# main.net
KiCad netlist of a schematic drawn in Altium Designer
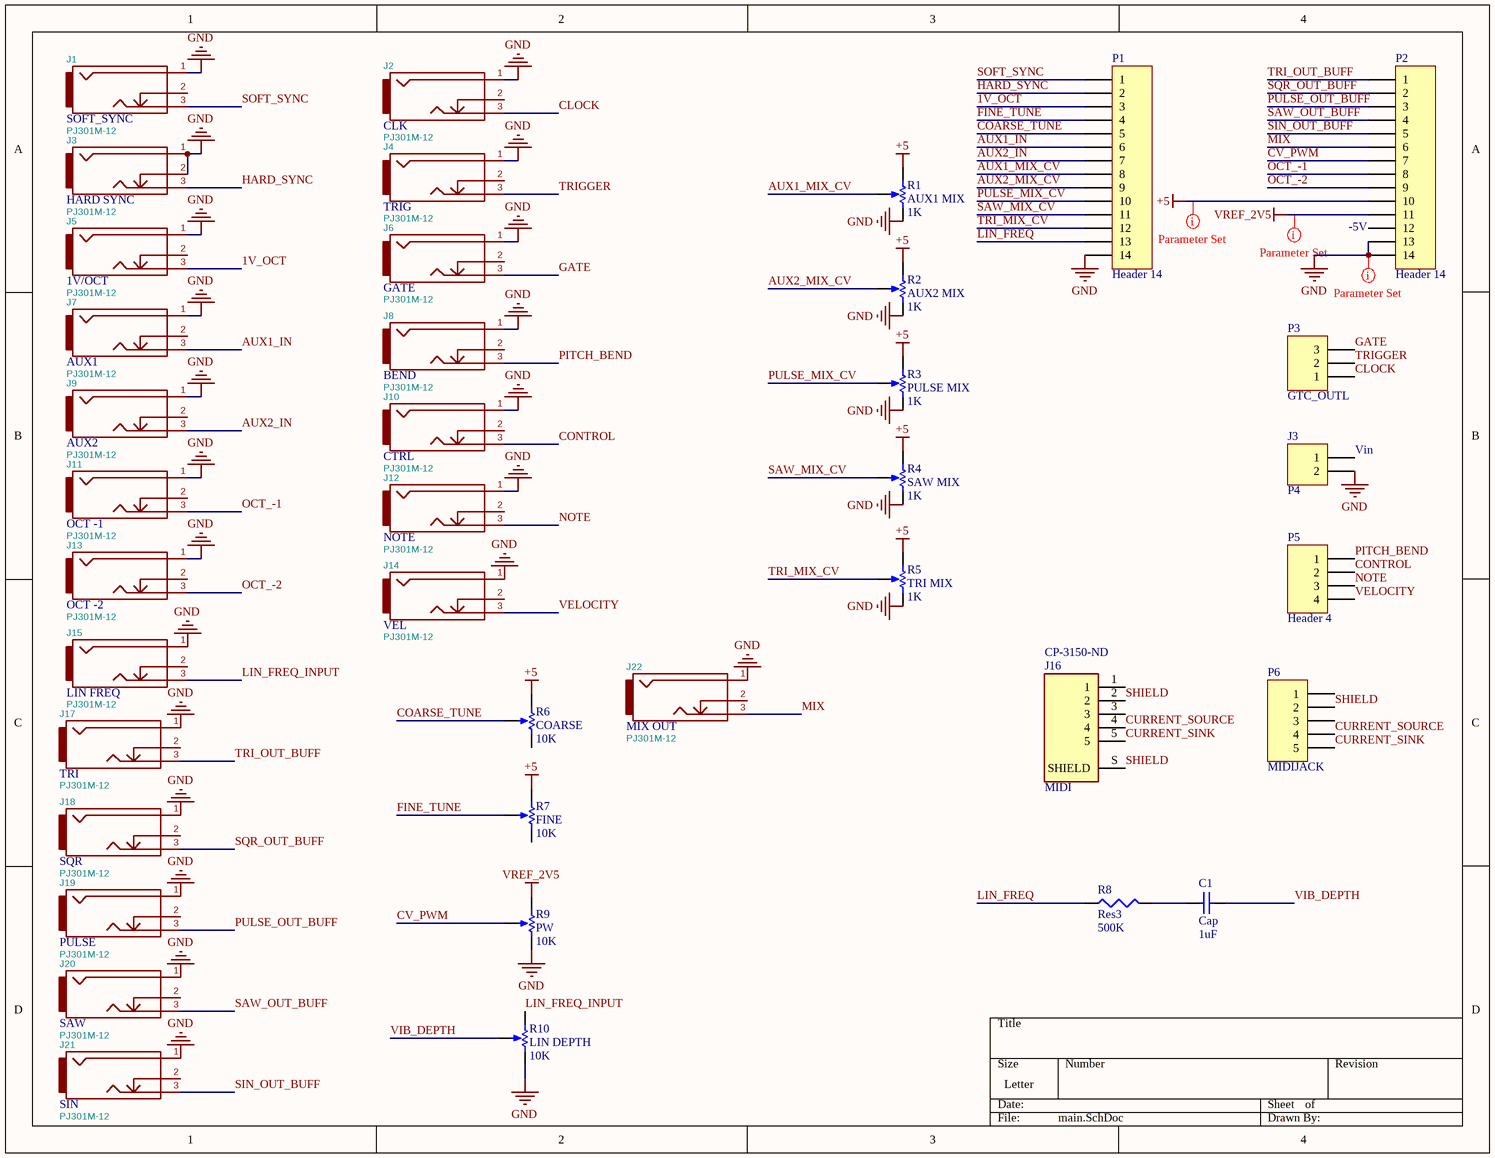
[diagram p0: main.SchDoc]

(export (version "E")
  (design (tool "Eeschema 10.0.6"))
  (components
    (comp (ref "C1")
      (value "Cap")
      (footprint "C1206")
      (description "Capacitor")
      (fields (field (name "ALTIUM_VALUE") "1uF") (field (name "PUBLISHER") "Altium Limited"))
      (libsource (lib "Miscellaneous Devices") (part "Cap"))
    )
    (comp (ref "J1")
      (value "SOFT_SYNC")
      (footprint "PJ301M-12")
      (fields (field (name "ALTIUM_VALUE") "PJ301M-12"))
      (libsource (lib "eurocad") (part "PJ301M-12"))
    )
    (comp (ref "J2")
      (value "CLK")
      (footprint "PJ301M-12")
      (fields (field (name "ALTIUM_VALUE") "PJ301M-12"))
      (libsource (lib "eurocad") (part "PJ301M-12"))
    )
    (comp (ref "J3")
      (value "HARD SYNC")
      (footprint "PJ301M-12")
      (fields (field (name "ALTIUM_VALUE") "PJ301M-12"))
      (libsource (lib "eurocad") (part "PJ301M-12"))
    )
    (comp (ref "J4")
      (value "TRIG")
      (footprint "PJ301M-12")
      (fields (field (name "ALTIUM_VALUE") "PJ301M-12"))
      (libsource (lib "eurocad") (part "PJ301M-12"))
    )
    (comp (ref "J5")
      (value "1V/OCT")
      (footprint "PJ301M-12")
      (fields (field (name "ALTIUM_VALUE") "PJ301M-12"))
      (libsource (lib "eurocad") (part "PJ301M-12"))
    )
    (comp (ref "J6")
      (value "GATE")
      (footprint "PJ301M-12")
      (fields (field (name "ALTIUM_VALUE") "PJ301M-12"))
      (libsource (lib "eurocad") (part "PJ301M-12"))
    )
    (comp (ref "J7")
      (value "AUX1")
      (footprint "PJ301M-12")
      (fields (field (name "ALTIUM_VALUE") "PJ301M-12"))
      (libsource (lib "eurocad") (part "PJ301M-12"))
    )
    (comp (ref "J8")
      (value "BEND")
      (footprint "PJ301M-12")
      (fields (field (name "ALTIUM_VALUE") "PJ301M-12"))
      (libsource (lib "eurocad") (part "PJ301M-12"))
    )
    (comp (ref "J9")
      (value "AUX2")
      (footprint "PJ301M-12")
      (fields (field (name "ALTIUM_VALUE") "PJ301M-12"))
      (libsource (lib "eurocad") (part "PJ301M-12"))
    )
    (comp (ref "J10")
      (value "CTRL")
      (footprint "PJ301M-12")
      (fields (field (name "ALTIUM_VALUE") "PJ301M-12"))
      (libsource (lib "eurocad") (part "PJ301M-12"))
    )
    (comp (ref "J11")
      (value "OCT -1")
      (footprint "PJ301M-12")
      (fields (field (name "ALTIUM_VALUE") "PJ301M-12"))
      (libsource (lib "eurocad") (part "PJ301M-12"))
    )
    (comp (ref "J12")
      (value "NOTE")
      (footprint "PJ301M-12")
      (fields (field (name "ALTIUM_VALUE") "PJ301M-12"))
      (libsource (lib "eurocad") (part "PJ301M-12"))
    )
    (comp (ref "J13")
      (value "OCT -2")
      (footprint "PJ301M-12")
      (fields (field (name "ALTIUM_VALUE") "PJ301M-12"))
      (libsource (lib "eurocad") (part "PJ301M-12"))
    )
    (comp (ref "J14")
      (value "VEL")
      (footprint "PJ301M-12")
      (fields (field (name "ALTIUM_VALUE") "PJ301M-12"))
      (libsource (lib "eurocad") (part "PJ301M-12"))
    )
    (comp (ref "J15")
      (value "LIN FREQ")
      (footprint "PJ301M-12")
      (fields (field (name "ALTIUM_VALUE") "PJ301M-12"))
      (libsource (lib "eurocad") (part "PJ301M-12"))
    )
    (comp (ref "J16")
      (value "MIDI")
      (footprint "CUI_SD-50BV")
      (description "3~8 Positions, Receptacle, Vertical, Through Hole, Shielded, Standard Circular DIN Connector")
      (fields
        (field (name "MP") "SD-50BV")
        (field (name "MF") "CUI Devices")
        (field (name "SUPPLIER PART NUMBER 1") "CP-3150-ND")
      )
      (libsource (lib "SD-50BV") (part "SD-50BV"))
    )
    (comp (ref "J17")
      (value "TRI")
      (footprint "PJ301M-12")
      (fields (field (name "ALTIUM_VALUE") "PJ301M-12"))
      (libsource (lib "eurocad") (part "PJ301M-12"))
    )
    (comp (ref "J18")
      (value "SQR")
      (footprint "PJ301M-12")
      (fields (field (name "ALTIUM_VALUE") "PJ301M-12"))
      (libsource (lib "eurocad") (part "PJ301M-12"))
    )
    (comp (ref "J19")
      (value "PULSE")
      (footprint "PJ301M-12")
      (fields (field (name "ALTIUM_VALUE") "PJ301M-12"))
      (libsource (lib "eurocad") (part "PJ301M-12"))
    )
    (comp (ref "J20")
      (value "SAW")
      (footprint "PJ301M-12")
      (fields (field (name "ALTIUM_VALUE") "PJ301M-12"))
      (libsource (lib "eurocad") (part "PJ301M-12"))
    )
    (comp (ref "J21")
      (value "SIN")
      (footprint "PJ301M-12")
      (fields (field (name "ALTIUM_VALUE") "PJ301M-12"))
      (libsource (lib "eurocad") (part "PJ301M-12"))
    )
    (comp (ref "J22")
      (value "MIX OUT")
      (footprint "PJ301M-12")
      (fields (field (name "ALTIUM_VALUE") "PJ301M-12"))
      (libsource (lib "eurocad") (part "PJ301M-12"))
    )
    (comp (ref "P1")
      (value "Header 14")
      (footprint "HDR1X14")
      (description "Header, 14-Pin")
      (fields (field (name "PUBLISHER") "Altium Limited"))
      (libsource (lib "Miscellaneous Connectors") (part "Header 14"))
    )
    (comp (ref "P2")
      (value "Header 14")
      (footprint "HDR1X14")
      (description "Header, 14-Pin")
      (fields (field (name "PUBLISHER") "Altium Limited"))
      (libsource (lib "Miscellaneous Connectors") (part "Header 14"))
    )
    (comp (ref "P3")
      (value "GTC_OUTL")
      (footprint "HDR1X3")
      (description "Header, 3-Pin")
      (fields (field (name "PUBLISHER") "Altium Limited"))
      (libsource (lib "Miscellaneous Connectors") (part "Header 3"))
    )
    (comp (ref "P4")
      (value "J3")
      (footprint "HDR1X2")
      (description "Header, 2-Pin")
      (fields (field (name "PUBLISHER") "Altium Limited"))
      (libsource (lib "Miscellaneous Connectors") (part "Header 2"))
    )
    (comp (ref "P5")
      (value "Header 4")
      (footprint "HDR1X4")
      (description "Header, 4-Pin")
      (fields (field (name "PUBLISHER") "Altium Limited"))
      (libsource (lib "Miscellaneous Connectors") (part "Header 4"))
    )
    (comp (ref "P6")
      (value "MIDIJACK")
      (footprint "HDR1X5")
      (description "Header, 5-Pin")
      (fields (field (name "PUBLISHER") "Altium Limited"))
      (libsource (lib "Miscellaneous Connectors") (part "Header 5"))
    )
    (comp (ref "R1")
      (value "AUX1 MIX")
      (footprint "Alpha9mmPot")
      (description "Potentiometer")
      (fields (field (name "ALTIUM_VALUE") "1K") (field (name "PUBLISHER") "Altium Limited"))
      (libsource (lib "Miscellaneous Devices") (part "RPot"))
    )
    (comp (ref "R2")
      (value "AUX2 MIX")
      (footprint "Alpha9mmPot")
      (description "Potentiometer")
      (fields (field (name "ALTIUM_VALUE") "1K") (field (name "PUBLISHER") "Altium Limited"))
      (libsource (lib "Miscellaneous Devices") (part "RPot"))
    )
    (comp (ref "R3")
      (value "PULSE MIX")
      (footprint "Alpha9mmPot")
      (description "Potentiometer")
      (fields (field (name "ALTIUM_VALUE") "1K") (field (name "PUBLISHER") "Altium Limited"))
      (libsource (lib "Miscellaneous Devices") (part "RPot"))
    )
    (comp (ref "R4")
      (value "SAW MIX")
      (footprint "Alpha9mmPot")
      (description "Potentiometer")
      (fields (field (name "ALTIUM_VALUE") "1K") (field (name "PUBLISHER") "Altium Limited"))
      (libsource (lib "Miscellaneous Devices") (part "RPot"))
    )
    (comp (ref "R5")
      (value "TRI MIX")
      (footprint "Alpha9mmPot")
      (description "Potentiometer")
      (fields (field (name "ALTIUM_VALUE") "1K") (field (name "PUBLISHER") "Altium Limited"))
      (libsource (lib "Miscellaneous Devices") (part "RPot"))
    )
    (comp (ref "R6")
      (value "COARSE")
      (footprint "Alpha9mmPot")
      (description "Potentiometer")
      (fields (field (name "ALTIUM_VALUE") "10K") (field (name "PUBLISHER") "Altium Limited"))
      (libsource (lib "Miscellaneous Devices") (part "RPot"))
    )
    (comp (ref "R7")
      (value "FINE")
      (footprint "Alpha9mmPot")
      (description "Potentiometer")
      (fields (field (name "ALTIUM_VALUE") "10K") (field (name "PUBLISHER") "Altium Limited"))
      (libsource (lib "Miscellaneous Devices") (part "RPot"))
    )
    (comp (ref "R8")
      (value "Res3")
      (footprint "C1206")
      (description "Resistor")
      (fields (field (name "ALTIUM_VALUE") "500K") (field (name "PUBLISHER") "Altium Limited"))
      (libsource (lib "Miscellaneous Devices") (part "Res3"))
    )
    (comp (ref "R9")
      (value "PW")
      (footprint "Alpha9mmPot")
      (description "Potentiometer")
      (fields (field (name "ALTIUM_VALUE") "10K") (field (name "PUBLISHER") "Altium Limited"))
      (libsource (lib "Miscellaneous Devices") (part "RPot"))
    )
    (comp (ref "R10")
      (value "LIN DEPTH")
      (footprint "Alpha9mmPot")
      (description "Potentiometer")
      (fields (field (name "ALTIUM_VALUE") "10K") (field (name "PUBLISHER") "Altium Limited"))
      (libsource (lib "Miscellaneous Devices") (part "RPot"))
    )
  )
  (nets
    (net (code "1") (name "+5") (class "Default")
      (node (ref "P2") (pin "10") (pinfunction "10_10") (pintype "passive"))
      (node (ref "R1") (pin "1") (pinfunction "TOP_1") (pintype "passive"))
      (node (ref "R2") (pin "1") (pinfunction "TOP_1") (pintype "passive"))
      (node (ref "R3") (pin "1") (pinfunction "TOP_1") (pintype "passive"))
      (node (ref "R4") (pin "1") (pinfunction "TOP_1") (pintype "passive"))
      (node (ref "R5") (pin "1") (pinfunction "TOP_1") (pintype "passive"))
      (node (ref "R6") (pin "1") (pinfunction "TOP_1") (pintype "passive"))
      (node (ref "R7") (pin "1") (pinfunction "TOP_1") (pintype "passive"))
    )
    (net (code "2") (name "/1V_OCT") (class "Default")
      (node (ref "J5") (pin "3") (pinfunction "3_3") (pintype "passive"))
      (node (ref "P1") (pin "3") (pinfunction "3_3") (pintype "passive"))
    )
    (net (code "3") (name "/AUX1_IN") (class "Default")
      (node (ref "J7") (pin "3") (pinfunction "3_3") (pintype "passive"))
      (node (ref "P1") (pin "6") (pinfunction "6_6") (pintype "passive"))
    )
    (net (code "4") (name "/AUX1_MIX_CV") (class "Default")
      (node (ref "P1") (pin "8") (pinfunction "8_8") (pintype "passive"))
      (node (ref "R1") (pin "3") (pinfunction "TAP_3") (pintype "passive"))
    )
    (net (code "5") (name "/AUX2_IN") (class "Default")
      (node (ref "J9") (pin "3") (pinfunction "3_3") (pintype "passive"))
      (node (ref "P1") (pin "7") (pinfunction "7_7") (pintype "passive"))
    )
    (net (code "6") (name "/AUX2_MIX_CV") (class "Default")
      (node (ref "P1") (pin "9") (pinfunction "9_9") (pintype "passive"))
      (node (ref "R2") (pin "3") (pinfunction "TAP_3") (pintype "passive"))
    )
    (net (code "7") (name "/CLOCK") (class "Default")
      (node (ref "J2") (pin "3") (pinfunction "3_3") (pintype "passive"))
      (node (ref "P3") (pin "1") (pinfunction "1_1") (pintype "passive"))
    )
    (net (code "8") (name "/COARSE_TUNE") (class "Default")
      (node (ref "P1") (pin "5") (pinfunction "5_5") (pintype "passive"))
      (node (ref "R6") (pin "3") (pinfunction "TAP_3") (pintype "passive"))
    )
    (net (code "9") (name "/CONTROL") (class "Default")
      (node (ref "J10") (pin "3") (pinfunction "3_3") (pintype "passive"))
      (node (ref "P5") (pin "2") (pinfunction "2_2") (pintype "passive"))
    )
    (net (code "10") (name "/CURRENT_SINK") (class "Default")
      (node (ref "J16") (pin "5") (pinfunction "5_5") (pintype "passive"))
      (node (ref "P6") (pin "5") (pinfunction "5_5") (pintype "passive"))
    )
    (net (code "11") (name "/CURRENT_SOURCE") (class "Default")
      (node (ref "J16") (pin "4") (pinfunction "4_4") (pintype "passive"))
      (node (ref "P6") (pin "4") (pinfunction "4_4") (pintype "passive"))
    )
    (net (code "12") (name "/CV_PWM") (class "Default")
      (node (ref "P2") (pin "7") (pinfunction "7_7") (pintype "passive"))
      (node (ref "R9") (pin "3") (pinfunction "TAP_3") (pintype "passive"))
    )
    (net (code "13") (name "/FINE_TUNE") (class "Default")
      (node (ref "P1") (pin "4") (pinfunction "4_4") (pintype "passive"))
      (node (ref "R7") (pin "3") (pinfunction "TAP_3") (pintype "passive"))
    )
    (net (code "14") (name "/GATE") (class "Default")
      (node (ref "J6") (pin "3") (pinfunction "3_3") (pintype "passive"))
      (node (ref "P3") (pin "3") (pinfunction "3_3") (pintype "passive"))
    )
    (net (code "15") (name "/HARD_SYNC") (class "Default")
      (node (ref "J3") (pin "3") (pinfunction "3_3") (pintype "passive"))
      (node (ref "P1") (pin "2") (pinfunction "2_2") (pintype "passive"))
    )
    (net (code "16") (name "/LIN_FREQ") (class "Default")
      (node (ref "P1") (pin "13") (pinfunction "13_13") (pintype "passive"))
      (node (ref "R8") (pin "1") (pinfunction "1_1") (pintype "passive"))
    )
    (net (code "17") (name "/LIN_FREQ_INPUT") (class "Default")
      (node (ref "J15") (pin "3") (pinfunction "3_3") (pintype "passive"))
      (node (ref "R10") (pin "1") (pinfunction "TOP_1") (pintype "passive"))
    )
    (net (code "18") (name "/MIX") (class "Default")
      (node (ref "J22") (pin "3") (pinfunction "3_3") (pintype "passive"))
      (node (ref "P2") (pin "6") (pinfunction "6_6") (pintype "passive"))
    )
    (net (code "19") (name "/NOTE") (class "Default")
      (node (ref "J12") (pin "3") (pinfunction "3_3") (pintype "passive"))
      (node (ref "P5") (pin "3") (pinfunction "3_3") (pintype "passive"))
    )
    (net (code "20") (name "/OCT_-1") (class "Default")
      (node (ref "J11") (pin "3") (pinfunction "3_3") (pintype "passive"))
      (node (ref "P2") (pin "8") (pinfunction "8_8") (pintype "passive"))
    )
    (net (code "21") (name "/OCT_-2") (class "Default")
      (node (ref "J13") (pin "3") (pinfunction "3_3") (pintype "passive"))
      (node (ref "P2") (pin "9") (pinfunction "9_9") (pintype "passive"))
    )
    (net (code "22") (name "/PITCH_BEND") (class "Default")
      (node (ref "J8") (pin "3") (pinfunction "3_3") (pintype "passive"))
      (node (ref "P5") (pin "1") (pinfunction "1_1") (pintype "passive"))
    )
    (net (code "23") (name "/PULSE_MIX_CV") (class "Default")
      (node (ref "P1") (pin "10") (pinfunction "10_10") (pintype "passive"))
      (node (ref "R3") (pin "3") (pinfunction "TAP_3") (pintype "passive"))
    )
    (net (code "24") (name "/PULSE_OUT_BUFF") (class "Default")
      (node (ref "J19") (pin "3") (pinfunction "3_3") (pintype "passive"))
      (node (ref "P2") (pin "3") (pinfunction "3_3") (pintype "passive"))
    )
    (net (code "25") (name "/SAW_MIX_CV") (class "Default")
      (node (ref "P1") (pin "11") (pinfunction "11_11") (pintype "passive"))
      (node (ref "R4") (pin "3") (pinfunction "TAP_3") (pintype "passive"))
    )
    (net (code "26") (name "/SAW_OUT_BUFF") (class "Default")
      (node (ref "J20") (pin "3") (pinfunction "3_3") (pintype "passive"))
      (node (ref "P2") (pin "4") (pinfunction "4_4") (pintype "passive"))
    )
    (net (code "27") (name "/SHIELD") (class "Default")
      (node (ref "J16") (pin "2") (pinfunction "2_2") (pintype "passive"))
      (node (ref "J16") (pin "S") (pinfunction "SHIELD_S") (pintype "passive"))
      (node (ref "P6") (pin "2") (pinfunction "2_2") (pintype "passive"))
    )
    (net (code "28") (name "/SIN_OUT_BUFF") (class "Default")
      (node (ref "J21") (pin "3") (pinfunction "3_3") (pintype "passive"))
      (node (ref "P2") (pin "5") (pinfunction "5_5") (pintype "passive"))
    )
    (net (code "29") (name "/SOFT_SYNC") (class "Default")
      (node (ref "J1") (pin "3") (pinfunction "3_3") (pintype "passive"))
      (node (ref "P1") (pin "1") (pinfunction "1_1") (pintype "passive"))
    )
    (net (code "30") (name "/SQR_OUT_BUFF") (class "Default")
      (node (ref "J18") (pin "3") (pinfunction "3_3") (pintype "passive"))
      (node (ref "P2") (pin "2") (pinfunction "2_2") (pintype "passive"))
    )
    (net (code "31") (name "/TRIGGER") (class "Default")
      (node (ref "J4") (pin "3") (pinfunction "3_3") (pintype "passive"))
      (node (ref "P3") (pin "2") (pinfunction "2_2") (pintype "passive"))
    )
    (net (code "32") (name "/TRI_MIX_CV") (class "Default")
      (node (ref "P1") (pin "12") (pinfunction "12_12") (pintype "passive"))
      (node (ref "R5") (pin "3") (pinfunction "TAP_3") (pintype "passive"))
    )
    (net (code "33") (name "/TRI_OUT_BUFF") (class "Default")
      (node (ref "J17") (pin "3") (pinfunction "3_3") (pintype "passive"))
      (node (ref "P2") (pin "1") (pinfunction "1_1") (pintype "passive"))
    )
    (net (code "34") (name "/VELOCITY") (class "Default")
      (node (ref "J14") (pin "3") (pinfunction "3_3") (pintype "passive"))
      (node (ref "P5") (pin "4") (pinfunction "4_4") (pintype "passive"))
    )
    (net (code "35") (name "/VIB_DEPTH") (class "Default")
      (node (ref "C1") (pin "2") (pinfunction "2_2") (pintype "passive"))
      (node (ref "R10") (pin "3") (pinfunction "TAP_3") (pintype "passive"))
    )
    (net (code "36") (name "GND") (class "Default")
      (node (ref "J1") (pin "1") (pinfunction "1_1") (pintype "passive"))
      (node (ref "J10") (pin "1") (pinfunction "1_1") (pintype "passive"))
      (node (ref "J11") (pin "1") (pinfunction "1_1") (pintype "passive"))
      (node (ref "J12") (pin "1") (pinfunction "1_1") (pintype "passive"))
      (node (ref "J13") (pin "1") (pinfunction "1_1") (pintype "passive"))
      (node (ref "J14") (pin "1") (pinfunction "1_1") (pintype "passive"))
      (node (ref "J15") (pin "1") (pinfunction "1_1") (pintype "passive"))
      (node (ref "J17") (pin "1") (pinfunction "1_1") (pintype "passive"))
      (node (ref "J18") (pin "1") (pinfunction "1_1") (pintype "passive"))
      (node (ref "J19") (pin "1") (pinfunction "1_1") (pintype "passive"))
      (node (ref "J2") (pin "1") (pinfunction "1_1") (pintype "passive"))
      (node (ref "J20") (pin "1") (pinfunction "1_1") (pintype "passive"))
      (node (ref "J21") (pin "1") (pinfunction "1_1") (pintype "passive"))
      (node (ref "J22") (pin "1") (pinfunction "1_1") (pintype "passive"))
      (node (ref "J3") (pin "1") (pinfunction "1_1") (pintype "passive"))
      (node (ref "J3") (pin "2") (pinfunction "2_2") (pintype "passive"))
      (node (ref "J4") (pin "1") (pinfunction "1_1") (pintype "passive"))
      (node (ref "J5") (pin "1") (pinfunction "1_1") (pintype "passive"))
      (node (ref "J6") (pin "1") (pinfunction "1_1") (pintype "passive"))
      (node (ref "J7") (pin "1") (pinfunction "1_1") (pintype "passive"))
      (node (ref "J8") (pin "1") (pinfunction "1_1") (pintype "passive"))
      (node (ref "J9") (pin "1") (pinfunction "1_1") (pintype "passive"))
      (node (ref "P1") (pin "14") (pinfunction "14_14") (pintype "passive"))
      (node (ref "P2") (pin "13") (pinfunction "13_13") (pintype "passive"))
      (node (ref "P2") (pin "14") (pinfunction "14_14") (pintype "passive"))
      (node (ref "P4") (pin "2") (pinfunction "2_2") (pintype "passive"))
      (node (ref "R1") (pin "2") (pinfunction "BOT_2") (pintype "passive"))
      (node (ref "R10") (pin "2") (pinfunction "BOT_2") (pintype "passive"))
      (node (ref "R2") (pin "2") (pinfunction "BOT_2") (pintype "passive"))
      (node (ref "R3") (pin "2") (pinfunction "BOT_2") (pintype "passive"))
      (node (ref "R4") (pin "2") (pinfunction "BOT_2") (pintype "passive"))
      (node (ref "R5") (pin "2") (pinfunction "BOT_2") (pintype "passive"))
      (node (ref "R9") (pin "2") (pinfunction "BOT_2") (pintype "passive"))
    )
    (net (code "37") (name "Net-(C1-Pad1)") (class "Default")
      (node (ref "C1") (pin "1") (pinfunction "1_1") (pintype "passive"))
      (node (ref "R8") (pin "2") (pinfunction "2_2") (pintype "passive"))
    )
    (net (code "38") (name "VREF_2V5") (class "Default")
      (node (ref "P2") (pin "11") (pinfunction "11_11") (pintype "passive"))
      (node (ref "R9") (pin "1") (pinfunction "TOP_1") (pintype "passive"))
    )
    (net (code "39") (name "unconnected-(J1-Pad2)") (class "Default")
      (node (ref "J1") (pin "2") (pinfunction "2_2") (pintype "passive"))
    )
    (net (code "40") (name "unconnected-(J2-Pad2)") (class "Default")
      (node (ref "J2") (pin "2") (pinfunction "2_2") (pintype "passive"))
    )
    (net (code "41") (name "unconnected-(J4-Pad2)") (class "Default")
      (node (ref "J4") (pin "2") (pinfunction "2_2") (pintype "passive"))
    )
    (net (code "42") (name "unconnected-(J5-Pad2)") (class "Default")
      (node (ref "J5") (pin "2") (pinfunction "2_2") (pintype "passive"))
    )
    (net (code "43") (name "unconnected-(J6-Pad2)") (class "Default")
      (node (ref "J6") (pin "2") (pinfunction "2_2") (pintype "passive"))
    )
    (net (code "44") (name "unconnected-(J7-Pad2)") (class "Default")
      (node (ref "J7") (pin "2") (pinfunction "2_2") (pintype "passive"))
    )
    (net (code "45") (name "unconnected-(J8-Pad2)") (class "Default")
      (node (ref "J8") (pin "2") (pinfunction "2_2") (pintype "passive"))
    )
    (net (code "46") (name "unconnected-(J9-Pad2)") (class "Default")
      (node (ref "J9") (pin "2") (pinfunction "2_2") (pintype "passive"))
    )
    (net (code "47") (name "unconnected-(J10-Pad2)") (class "Default")
      (node (ref "J10") (pin "2") (pinfunction "2_2") (pintype "passive"))
    )
    (net (code "48") (name "unconnected-(J11-Pad2)") (class "Default")
      (node (ref "J11") (pin "2") (pinfunction "2_2") (pintype "passive"))
    )
    (net (code "49") (name "unconnected-(J12-Pad2)") (class "Default")
      (node (ref "J12") (pin "2") (pinfunction "2_2") (pintype "passive"))
    )
    (net (code "50") (name "unconnected-(J13-Pad2)") (class "Default")
      (node (ref "J13") (pin "2") (pinfunction "2_2") (pintype "passive"))
    )
    (net (code "51") (name "unconnected-(J14-Pad2)") (class "Default")
      (node (ref "J14") (pin "2") (pinfunction "2_2") (pintype "passive"))
    )
    (net (code "52") (name "unconnected-(J15-Pad2)") (class "Default")
      (node (ref "J15") (pin "2") (pinfunction "2_2") (pintype "passive"))
    )
    (net (code "53") (name "unconnected-(J16-Pad1)") (class "Default")
      (node (ref "J16") (pin "1") (pinfunction "1_1") (pintype "passive"))
    )
    (net (code "54") (name "unconnected-(J16-Pad3)") (class "Default")
      (node (ref "J16") (pin "3") (pinfunction "3_3") (pintype "passive"))
    )
    (net (code "55") (name "unconnected-(J17-Pad2)") (class "Default")
      (node (ref "J17") (pin "2") (pinfunction "2_2") (pintype "passive"))
    )
    (net (code "56") (name "unconnected-(J18-Pad2)") (class "Default")
      (node (ref "J18") (pin "2") (pinfunction "2_2") (pintype "passive"))
    )
    (net (code "57") (name "unconnected-(J19-Pad2)") (class "Default")
      (node (ref "J19") (pin "2") (pinfunction "2_2") (pintype "passive"))
    )
    (net (code "58") (name "unconnected-(J20-Pad2)") (class "Default")
      (node (ref "J20") (pin "2") (pinfunction "2_2") (pintype "passive"))
    )
    (net (code "59") (name "unconnected-(J21-Pad2)") (class "Default")
      (node (ref "J21") (pin "2") (pinfunction "2_2") (pintype "passive"))
    )
    (net (code "60") (name "unconnected-(J22-Pad2)") (class "Default")
      (node (ref "J22") (pin "2") (pinfunction "2_2") (pintype "passive"))
    )
    (net (code "61") (name "unconnected-(P2-Pad12)") (class "Default")
      (node (ref "P2") (pin "12") (pinfunction "12_12") (pintype "passive"))
    )
    (net (code "62") (name "unconnected-(P4-Pad1)") (class "Default")
      (node (ref "P4") (pin "1") (pinfunction "1_1") (pintype "passive"))
    )
    (net (code "63") (name "unconnected-(P6-Pad1)") (class "Default")
      (node (ref "P6") (pin "1") (pinfunction "1_1") (pintype "passive"))
    )
    (net (code "64") (name "unconnected-(P6-Pad3)") (class "Default")
      (node (ref "P6") (pin "3") (pinfunction "3_3") (pintype "passive"))
    )
    (net (code "65") (name "unconnected-(R6-BOT-Pad2)") (class "Default")
      (node (ref "R6") (pin "2") (pinfunction "BOT_2") (pintype "passive"))
    )
    (net (code "66") (name "unconnected-(R7-BOT-Pad2)") (class "Default")
      (node (ref "R7") (pin "2") (pinfunction "BOT_2") (pintype "passive"))
    )
  )
)
